# guitar_pedal.net
KiCad netlist of a schematic drawn in EAGLE
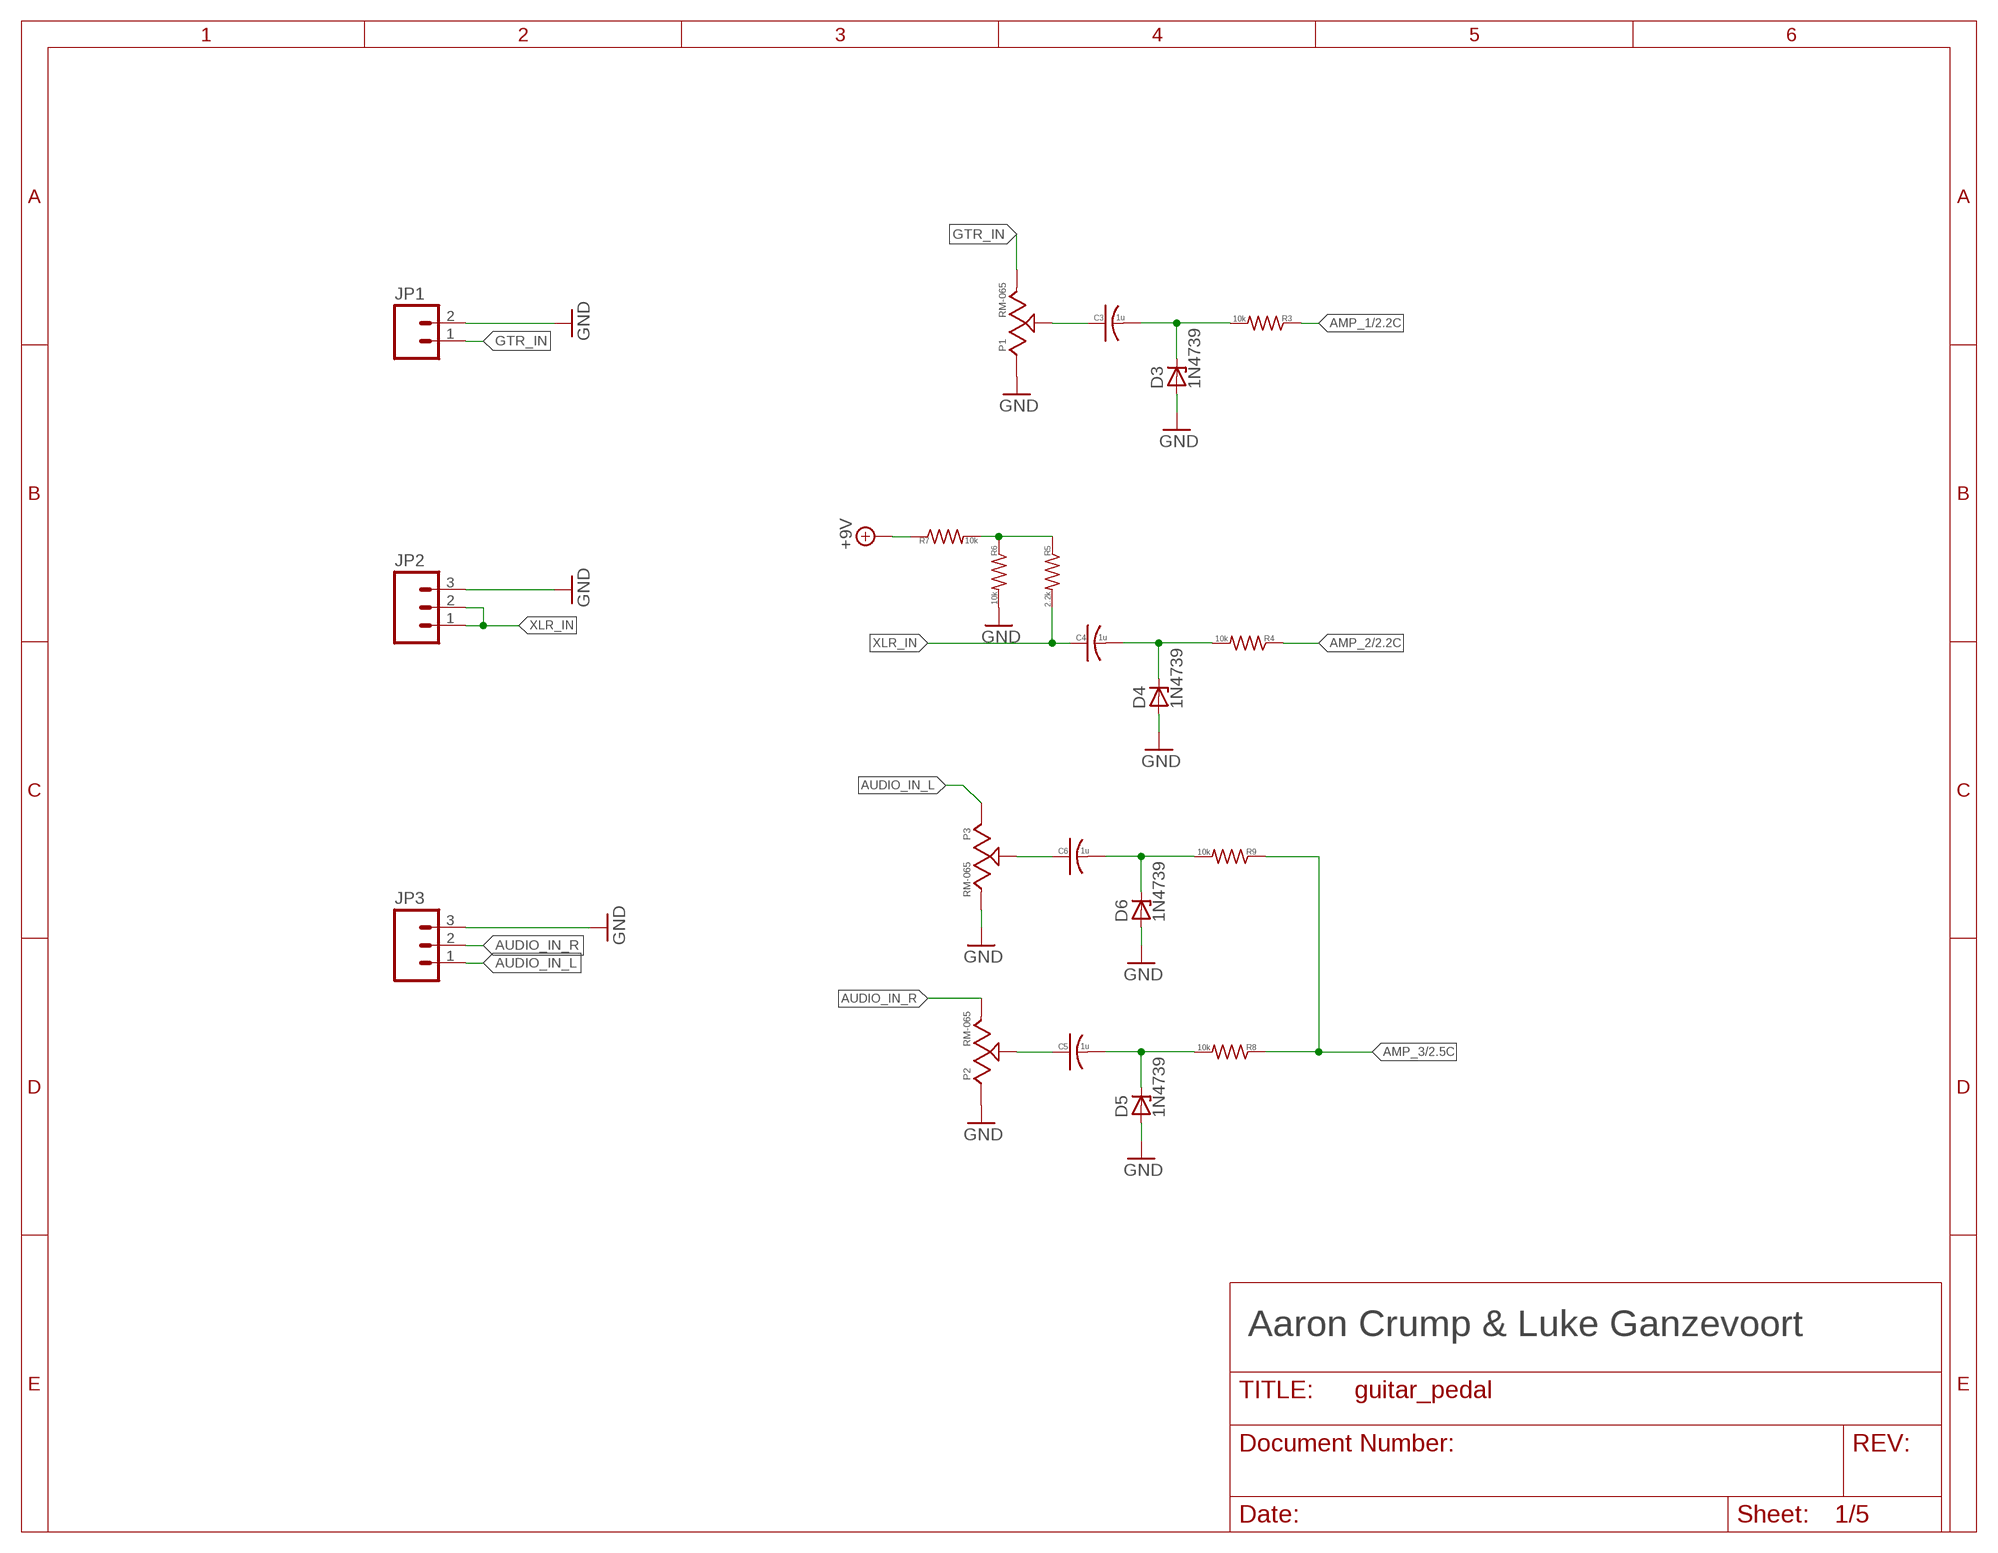
[diagram p0: schematic, sheet 1]
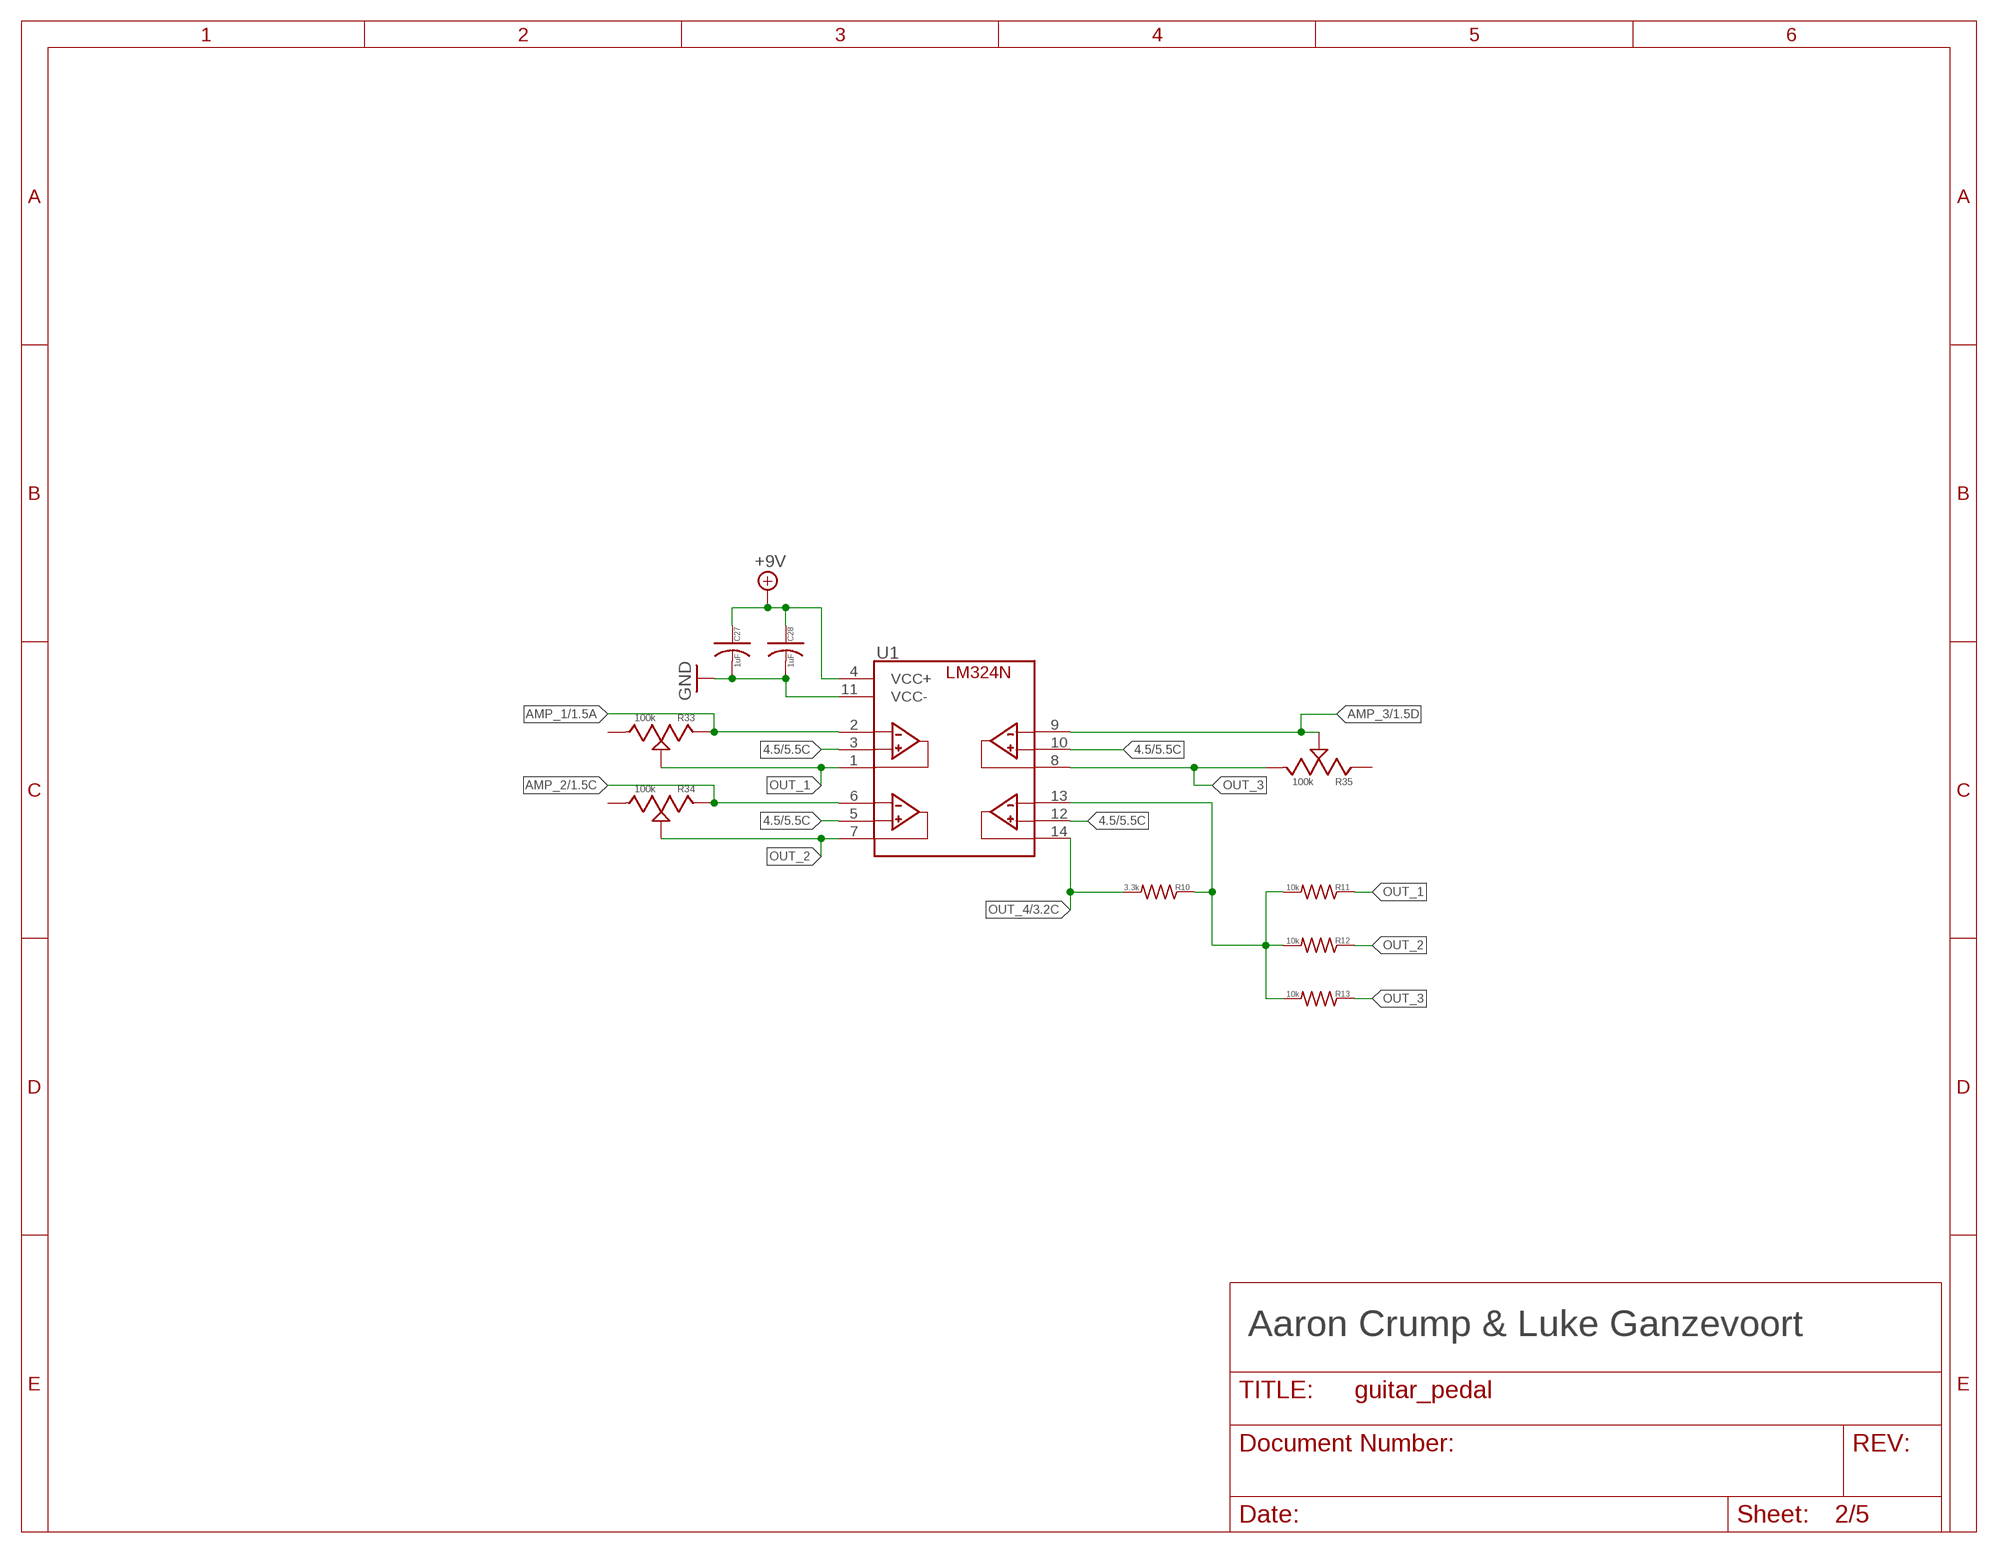
[diagram p1: schematic, sheet 2]
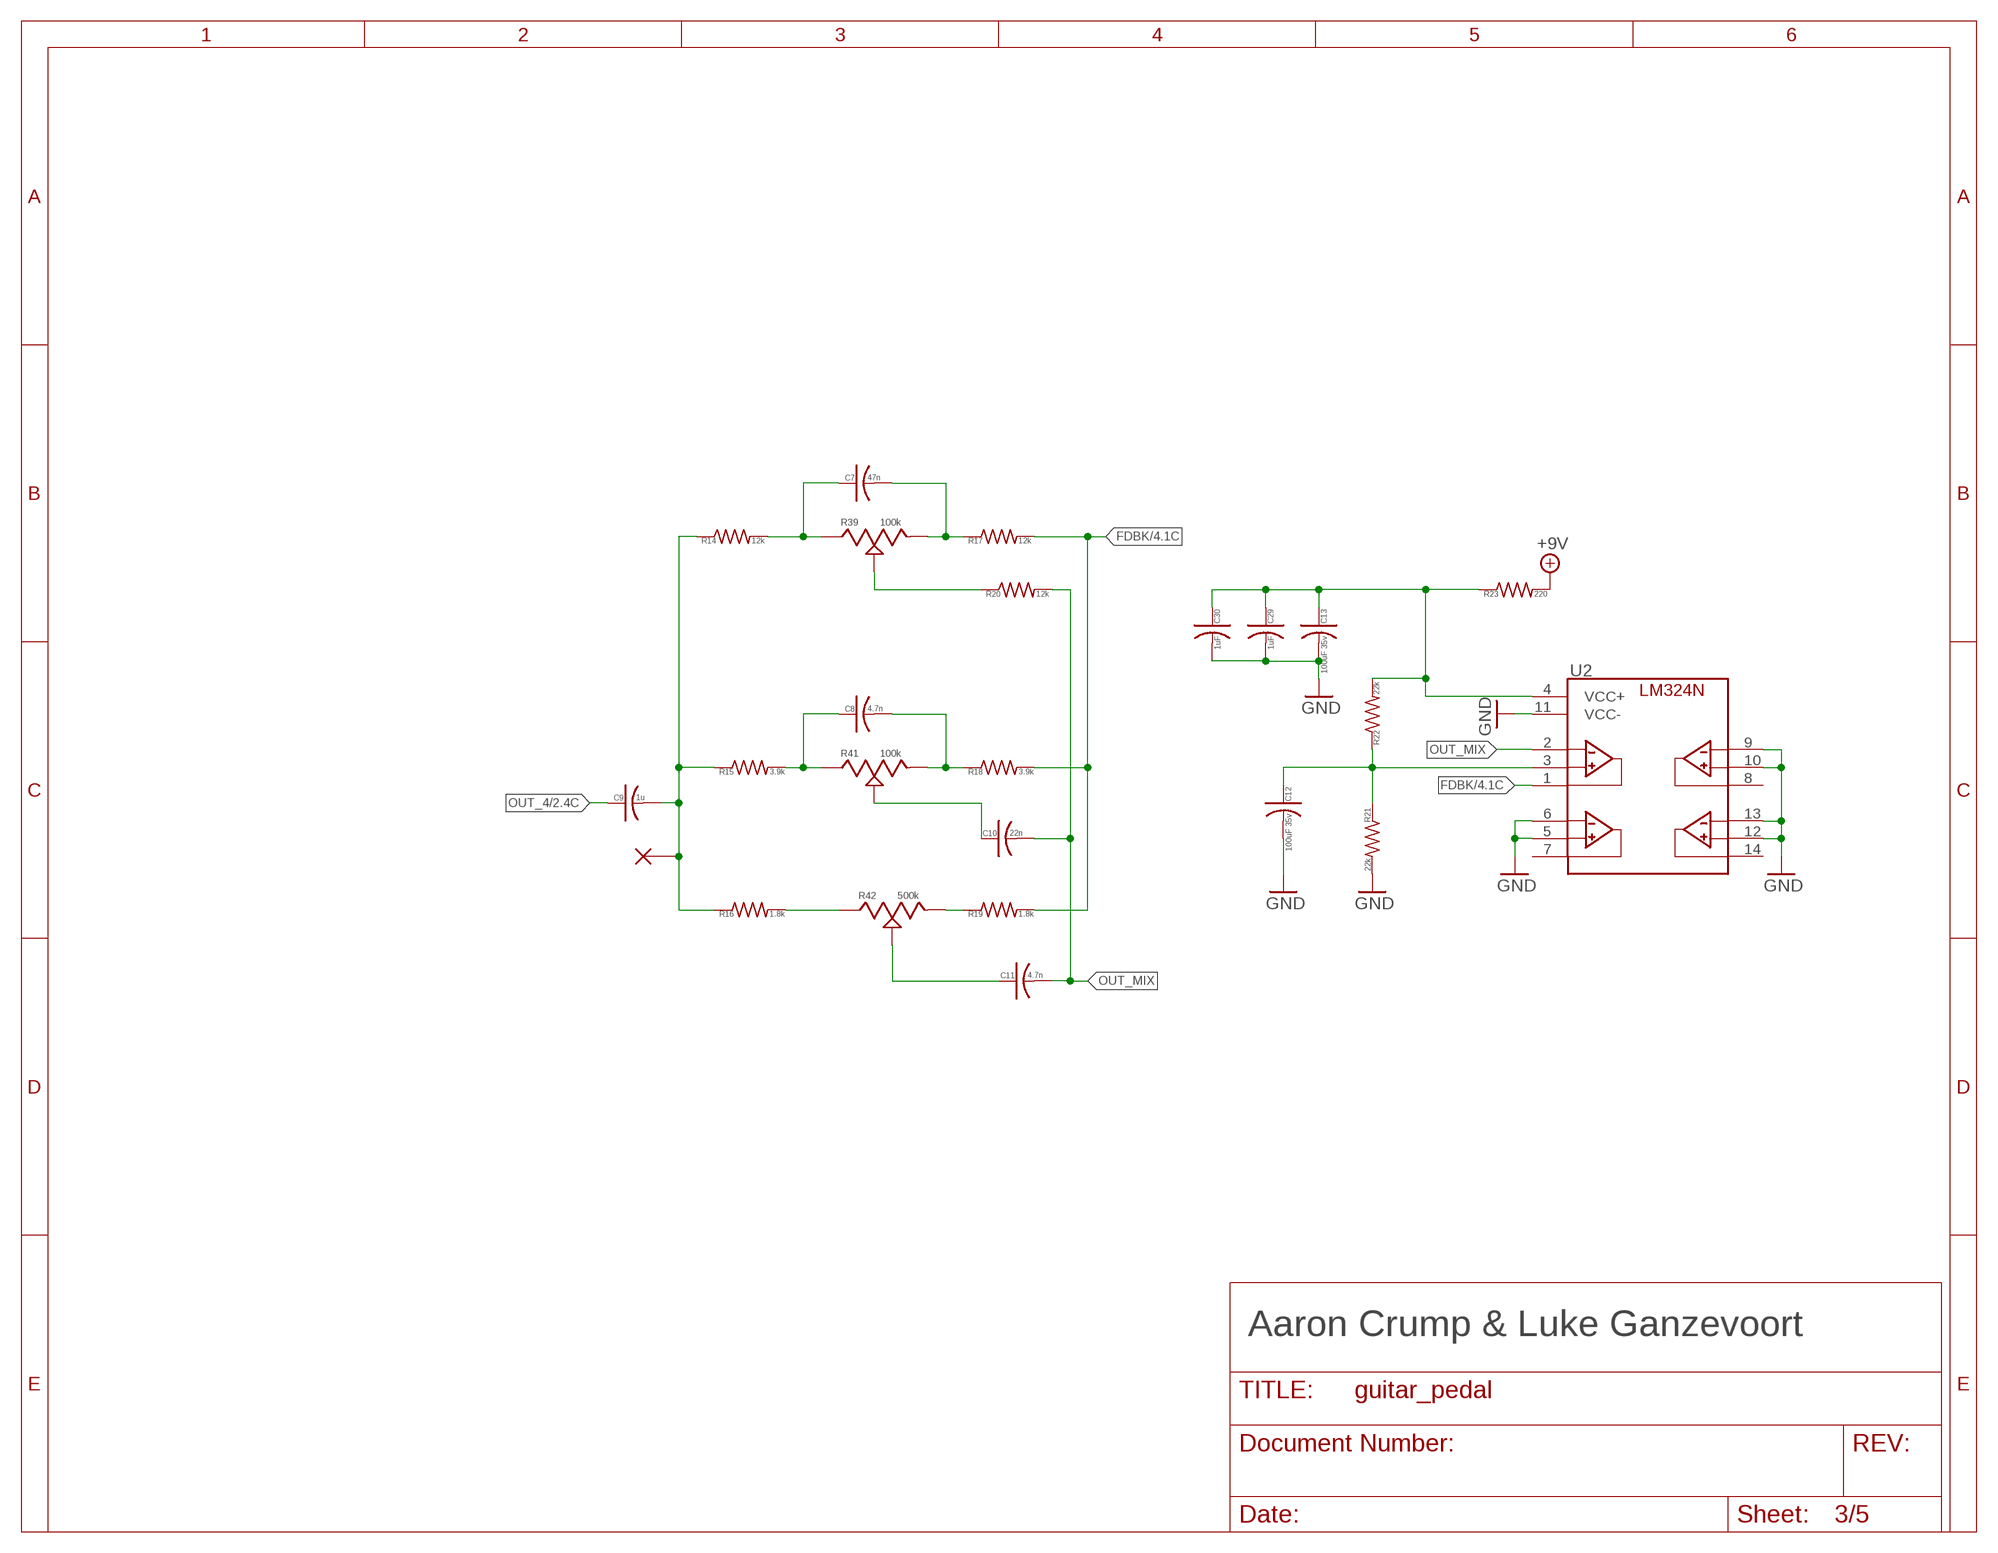
[diagram p2: schematic, sheet 3]
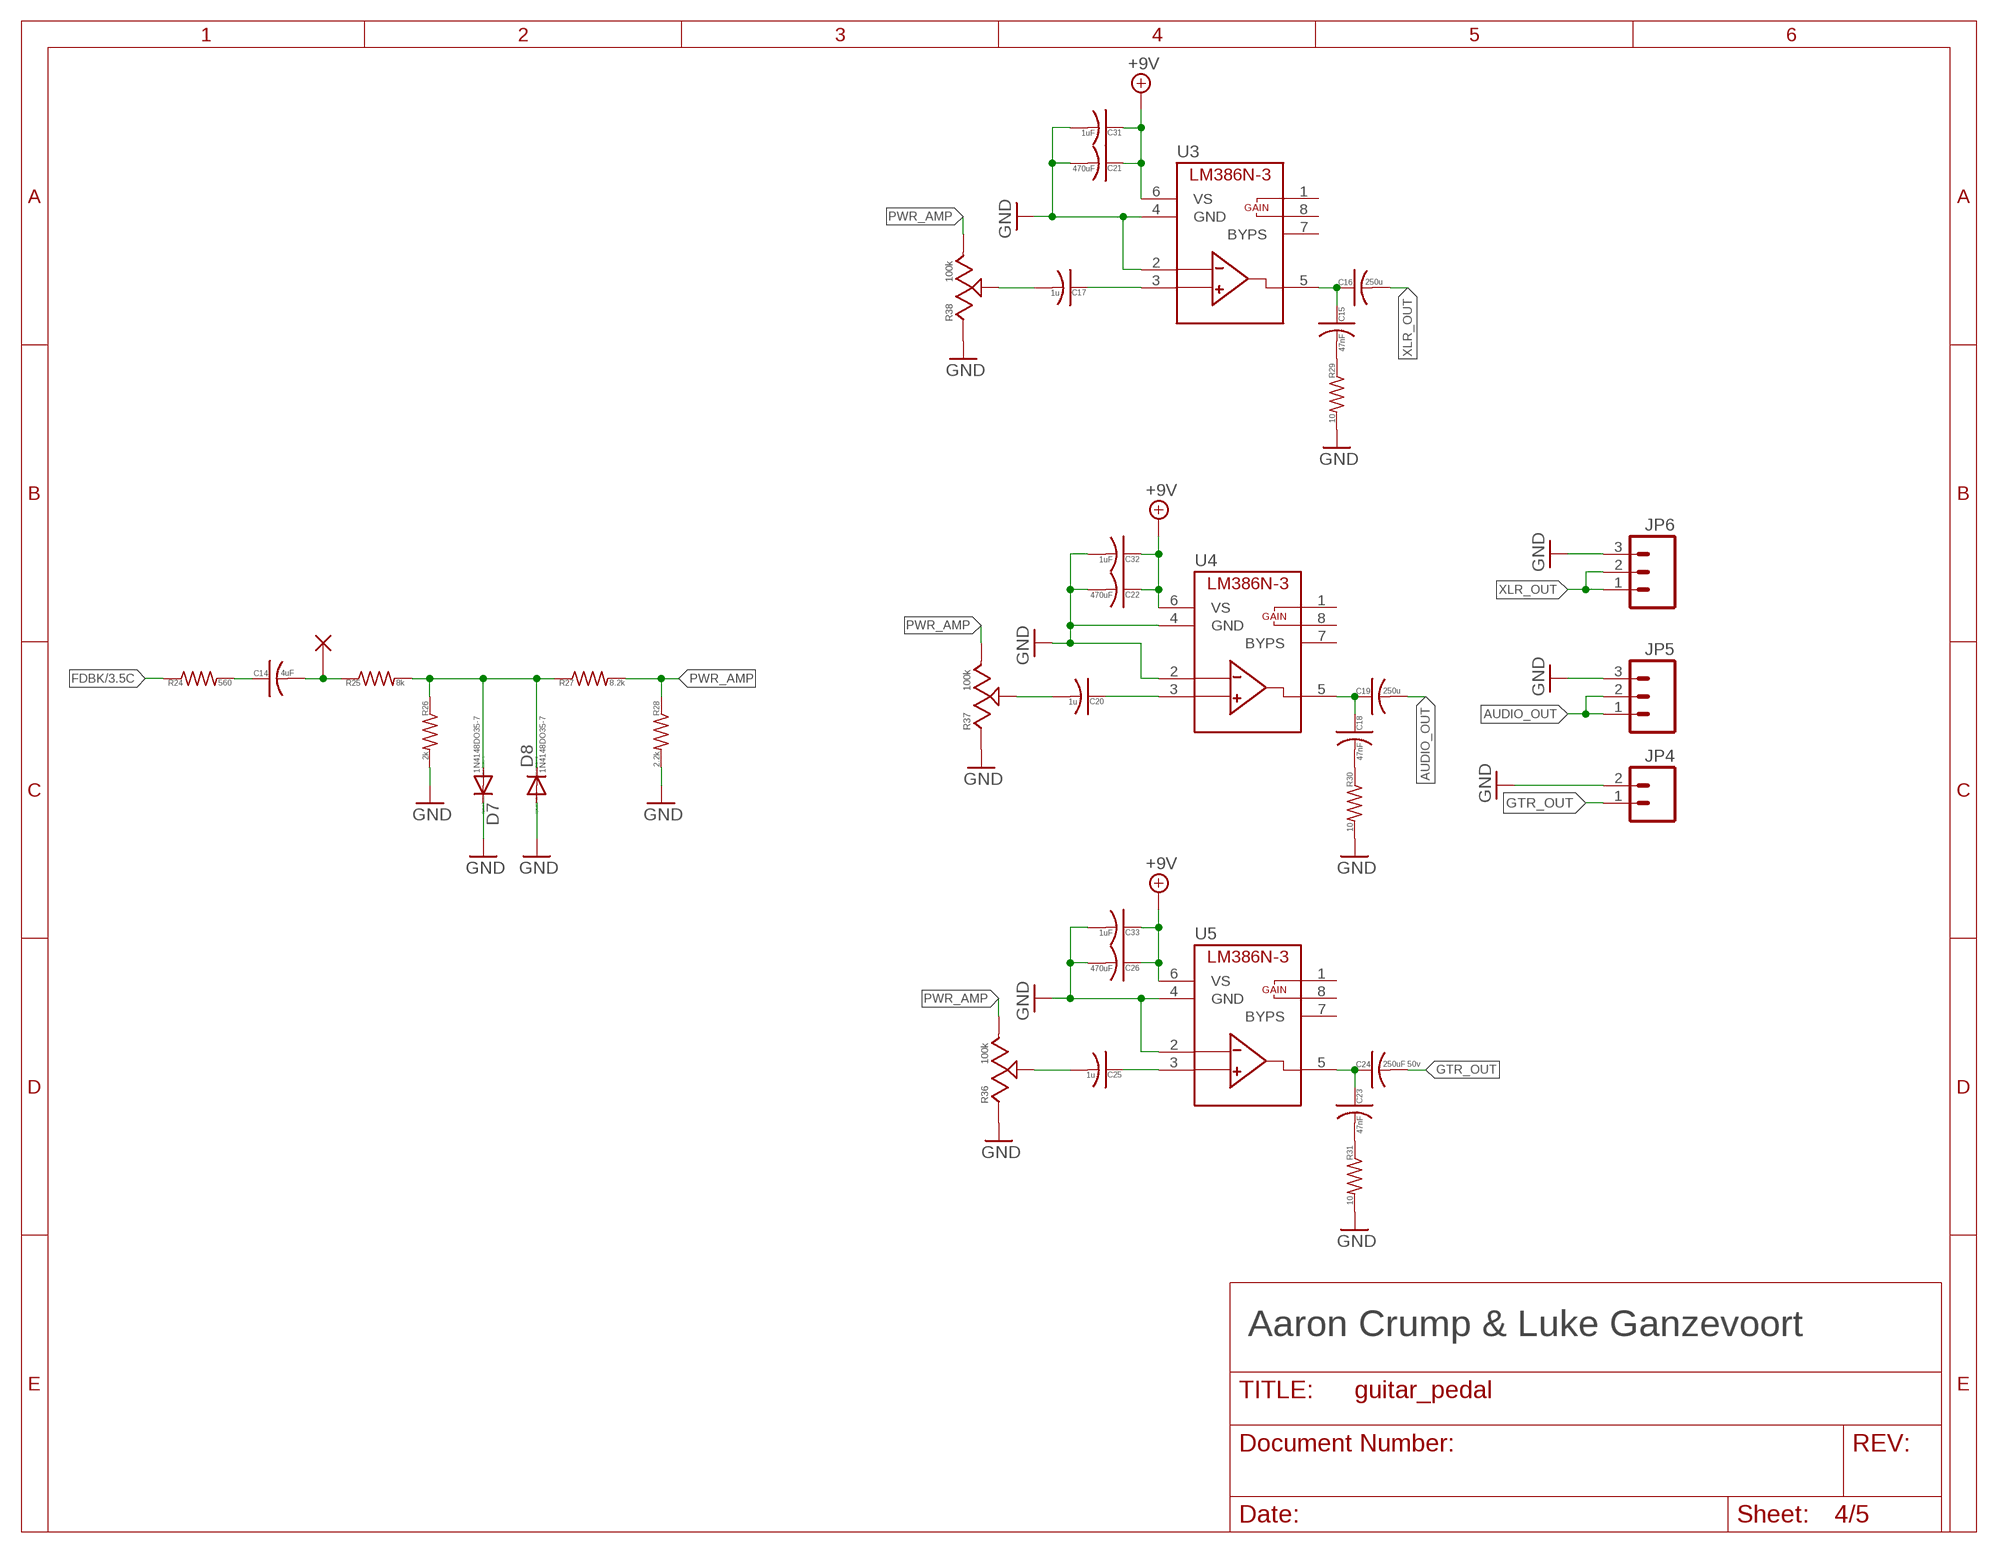
[diagram p3: schematic, sheet 4]
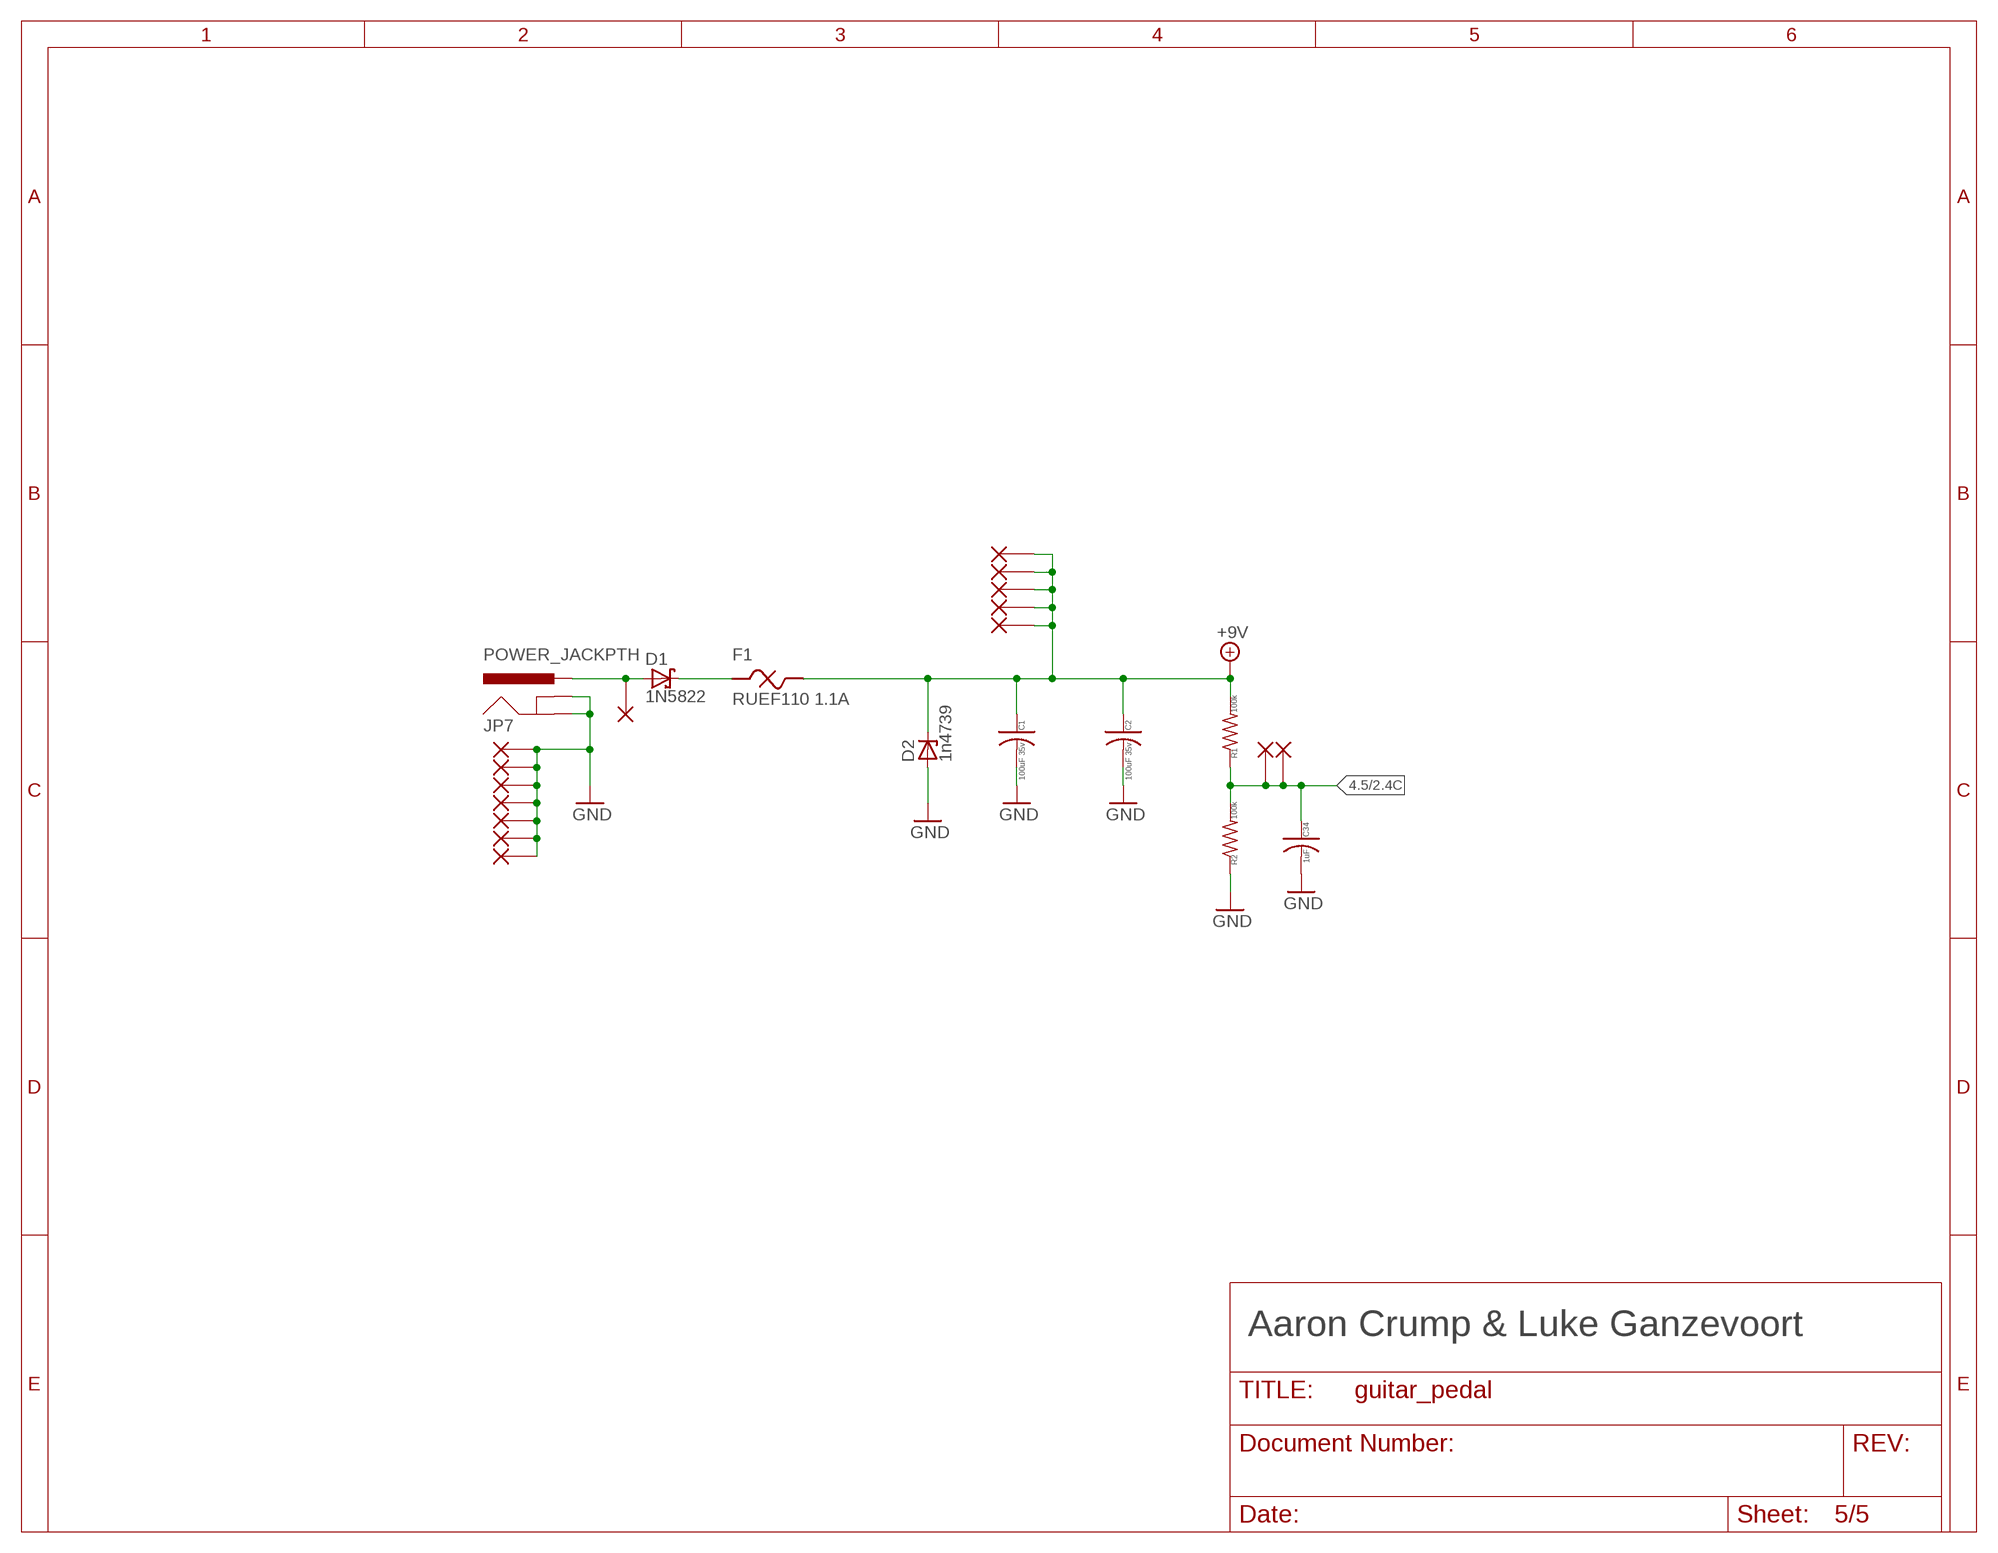
[diagram p4: schematic, sheet 5]

(export (version "E")
  (design (tool "Eeschema 10.0.6"))
  (components
    (comp (ref "C14")
      (value "4uF")
      (footprint "eagle-import:C0805")
      (libsource (lib "eagle-import") (part "CAPACITOR0805"))
    )
    (comp (ref "C15")
      (value "47nF")
      (footprint "eagle-import:C0805")
      (libsource (lib "eagle-import") (part "CAPACITOR0805"))
    )
    (comp (ref "C16")
      (value "250u")
      (footprint "eagle-import:CAN01")
      (libsource (lib "eagle-import") (part "CAP_CAN01"))
    )
    (comp (ref "C17")
      (value "1u")
      (footprint "eagle-import:C0805")
      (libsource (lib "eagle-import") (part "CAPACITOR0805"))
    )
    (comp (ref "C18")
      (value "47nF")
      (footprint "eagle-import:C0805")
      (libsource (lib "eagle-import") (part "CAPACITOR0805"))
    )
    (comp (ref "C19")
      (value "250u")
      (footprint "eagle-import:CAN01")
      (libsource (lib "eagle-import") (part "CAP_CAN01"))
    )
    (comp (ref "C20")
      (value "1u")
      (footprint "eagle-import:C0805")
      (libsource (lib "eagle-import") (part "CAPACITOR0805"))
    )
    (comp (ref "C21")
      (value "470uF")
      (footprint "eagle-import:CAN01")
      (libsource (lib "eagle-import") (part "CAP_CAN01"))
    )
    (comp (ref "C22")
      (value "470uF")
      (footprint "eagle-import:CAN01")
      (libsource (lib "eagle-import") (part "CAP_CAN01"))
    )
    (comp (ref "C23")
      (value "47nF")
      (footprint "eagle-import:C0805")
      (libsource (lib "eagle-import") (part "CAPACITOR0805"))
    )
    (comp (ref "C24")
      (value "250uF 50v")
      (footprint "eagle-import:CAN01")
      (libsource (lib "eagle-import") (part "CAP_CAN01"))
    )
    (comp (ref "C25")
      (value "1u")
      (footprint "eagle-import:C0805")
      (libsource (lib "eagle-import") (part "CAPACITOR0805"))
    )
    (comp (ref "C26")
      (value "470uF")
      (footprint "eagle-import:CAN01")
      (libsource (lib "eagle-import") (part "CAP_CAN01"))
    )
    (comp (ref "C31")
      (value "1uF")
      (footprint "eagle-import:C0805")
      (libsource (lib "eagle-import") (part "CAPACITOR0805"))
    )
    (comp (ref "C32")
      (value "1uF")
      (footprint "eagle-import:C0805")
      (libsource (lib "eagle-import") (part "CAPACITOR0805"))
    )
    (comp (ref "C33")
      (value "1uF")
      (footprint "eagle-import:C0805")
      (libsource (lib "eagle-import") (part "CAPACITOR0805"))
    )
    (comp (ref "D7")
      (value "1N4148DO35-7")
      (footprint "eagle-import:DO35-7")
      (libsource (lib "eagle-import") (part "1N4148DO35-7"))
    )
    (comp (ref "D8")
      (value "1N4148DO35-7")
      (footprint "eagle-import:DO35-7")
      (libsource (lib "eagle-import") (part "1N4148DO35-7"))
    )
    (comp (ref "JP4")
      (value "M02PTH")
      (footprint "eagle-import:1X02")
      (libsource (lib "eagle-import") (part "M02PTH"))
    )
    (comp (ref "JP5")
      (value "M03PTH")
      (footprint "eagle-import:1X03")
      (libsource (lib "eagle-import") (part "M03PTH"))
    )
    (comp (ref "JP6")
      (value "M03PTH")
      (footprint "eagle-import:1X03")
      (libsource (lib "eagle-import") (part "M03PTH"))
    )
    (comp (ref "R24")
      (value "560")
      (footprint "eagle-import:C0805")
      (libsource (lib "eagle-import") (part "RESISTOR0805"))
    )
    (comp (ref "R25")
      (value "8k")
      (footprint "eagle-import:C0805")
      (libsource (lib "eagle-import") (part "RESISTOR0805"))
    )
    (comp (ref "R26")
      (value "2k")
      (footprint "eagle-import:C0805")
      (libsource (lib "eagle-import") (part "RESISTOR0805"))
    )
    (comp (ref "R27")
      (value "8.2k")
      (footprint "eagle-import:C0805")
      (libsource (lib "eagle-import") (part "RESISTOR0805"))
    )
    (comp (ref "R28")
      (value "2.2k")
      (footprint "eagle-import:C0805")
      (libsource (lib "eagle-import") (part "RESISTOR0805"))
    )
    (comp (ref "R29")
      (value "10")
      (footprint "eagle-import:C0805")
      (libsource (lib "eagle-import") (part "RESISTOR0805"))
    )
    (comp (ref "R30")
      (value "10")
      (footprint "eagle-import:C0805")
      (libsource (lib "eagle-import") (part "RESISTOR0805"))
    )
    (comp (ref "R31")
      (value "10")
      (footprint "eagle-import:C0805")
      (libsource (lib "eagle-import") (part "RESISTOR0805"))
    )
    (comp (ref "R36")
      (value "100k")
      (footprint "eagle-import:1X03_LONGPADS")
      (libsource (lib "eagle-import") (part "POT"))
    )
    (comp (ref "R37")
      (value "100k")
      (footprint "eagle-import:1X03_LONGPADS")
      (libsource (lib "eagle-import") (part "POT"))
    )
    (comp (ref "R38")
      (value "100k")
      (footprint "eagle-import:1X03_LONGPADS")
      (libsource (lib "eagle-import") (part "POT"))
    )
    (comp (ref "U3")
      (value "LM386N-3")
      (footprint "eagle-import:DIL08")
      (libsource (lib "eagle-import") (part "LM386N-3"))
    )
    (comp (ref "U4")
      (value "LM386N-3")
      (footprint "eagle-import:DIL08")
      (libsource (lib "eagle-import") (part "LM386N-3"))
    )
    (comp (ref "U5")
      (value "LM386N-3")
      (footprint "eagle-import:DIL08")
      (libsource (lib "eagle-import") (part "LM386N-3"))
    )
    (comp (ref "V17")
      (value "EQout")
      (footprint "eagle-import:VIA1")
      (libsource (lib "eagle-import") (part "VIA1"))
    )
    (comp (ref "C1")
      (value "100uF 35v")
      (footprint "eagle-import:CAN_6MM")
      (libsource (lib "eagle-import") (part "CAPACITORCAN_6MM"))
    )
    (comp (ref "C2")
      (value "100uF 35v")
      (footprint "eagle-import:CAN_6MM")
      (libsource (lib "eagle-import") (part "CAPACITORCAN_6MM"))
    )
    (comp (ref "C34")
      (value "1uF")
      (footprint "eagle-import:C0805")
      (libsource (lib "eagle-import") (part "CAPACITOR0805"))
    )
    (comp (ref "D1")
      (value "1N5822")
      (footprint "eagle-import:DO201T15")
      (libsource (lib "eagle-import") (part "1N5822"))
    )
    (comp (ref "D2")
      (value "1n4739")
      (footprint "eagle-import:DO41-7")
      (libsource (lib "eagle-import") (part "1N4728"))
    )
    (comp (ref "F1")
      (value "RUEF110 1.1A")
      (footprint "eagle-import:RADIAL_PTC_RUEF110")
      (libsource (lib "eagle-import") (part "PTCRUEF110"))
    )
    (comp (ref "JP7")
      (value "POWER_JACKPTH")
      (footprint "eagle-import:POWER_JACK_PTH")
      (libsource (lib "eagle-import") (part "POWER_JACKPTH"))
    )
    (comp (ref "R1")
      (value "100k")
      (footprint "eagle-import:C0805")
      (libsource (lib "eagle-import") (part "RESISTOR0805"))
    )
    (comp (ref "R2")
      (value "100k")
      (footprint "eagle-import:C0805")
      (libsource (lib "eagle-import") (part "RESISTOR0805"))
    )
    (comp (ref "V1")
      (value "V+")
      (footprint "eagle-import:VIA1")
      (libsource (lib "eagle-import") (part "VIA1"))
    )
    (comp (ref "V3")
      (value "9v")
      (footprint "eagle-import:VIA1")
      (libsource (lib "eagle-import") (part "VIA1"))
    )
    (comp (ref "V4")
      (value "9v")
      (footprint "eagle-import:VIA1")
      (libsource (lib "eagle-import") (part "VIA1"))
    )
    (comp (ref "V5")
      (value "9v")
      (footprint "eagle-import:VIA1")
      (libsource (lib "eagle-import") (part "VIA1"))
    )
    (comp (ref "V6")
      (value "9v")
      (footprint "eagle-import:VIA1")
      (libsource (lib "eagle-import") (part "VIA1"))
    )
    (comp (ref "V7")
      (value "9v")
      (footprint "eagle-import:VIA1")
      (libsource (lib "eagle-import") (part "VIA1"))
    )
    (comp (ref "V8")
      (value "4v5")
      (footprint "eagle-import:VIA1")
      (libsource (lib "eagle-import") (part "VIA1"))
    )
    (comp (ref "V9")
      (value "4v5")
      (footprint "eagle-import:VIA1")
      (libsource (lib "eagle-import") (part "VIA1"))
    )
    (comp (ref "V10")
      (value "GND")
      (footprint "eagle-import:VIA1")
      (libsource (lib "eagle-import") (part "VIA1"))
    )
    (comp (ref "V11")
      (value "GND")
      (footprint "eagle-import:VIA1")
      (libsource (lib "eagle-import") (part "VIA1"))
    )
    (comp (ref "V12")
      (value "GND")
      (footprint "eagle-import:VIA1")
      (libsource (lib "eagle-import") (part "VIA1"))
    )
    (comp (ref "V13")
      (value "GND")
      (footprint "eagle-import:VIA1")
      (libsource (lib "eagle-import") (part "VIA1"))
    )
    (comp (ref "V14")
      (value "GND")
      (footprint "eagle-import:VIA1")
      (libsource (lib "eagle-import") (part "VIA1"))
    )
    (comp (ref "V15")
      (value "GND")
      (footprint "eagle-import:VIA1")
      (libsource (lib "eagle-import") (part "VIA1"))
    )
    (comp (ref "V16")
      (value "GND")
      (footprint "eagle-import:VIA1")
      (libsource (lib "eagle-import") (part "VIA1"))
    )
    (comp (ref "C7")
      (value "47n")
      (footprint "eagle-import:C0805")
      (libsource (lib "eagle-import") (part "CAPACITOR0805"))
    )
    (comp (ref "C8")
      (value "4.7n")
      (footprint "eagle-import:C0805")
      (libsource (lib "eagle-import") (part "CAPACITOR0805"))
    )
    (comp (ref "C9")
      (value "1u")
      (footprint "eagle-import:C0805")
      (libsource (lib "eagle-import") (part "CAPACITOR0805"))
    )
    (comp (ref "C10")
      (value "22n")
      (footprint "eagle-import:C0805")
      (libsource (lib "eagle-import") (part "CAPACITOR0805"))
    )
    (comp (ref "C11")
      (value "4.7n")
      (footprint "eagle-import:C0805")
      (libsource (lib "eagle-import") (part "CAPACITOR0805"))
    )
    (comp (ref "C12")
      (value "100uF 35v")
      (footprint "eagle-import:CAN_6MM")
      (libsource (lib "eagle-import") (part "CAPACITORCAN_6MM"))
    )
    (comp (ref "C13")
      (value "100uF 35v")
      (footprint "eagle-import:CAN_6MM")
      (libsource (lib "eagle-import") (part "CAPACITORCAN_6MM"))
    )
    (comp (ref "C29")
      (value "1uF")
      (footprint "eagle-import:C0805")
      (libsource (lib "eagle-import") (part "CAPACITOR0805"))
    )
    (comp (ref "C30")
      (value "1uF")
      (footprint "eagle-import:C0805")
      (libsource (lib "eagle-import") (part "CAPACITOR0805"))
    )
    (comp (ref "R14")
      (value "12k")
      (footprint "eagle-import:C0805")
      (libsource (lib "eagle-import") (part "RESISTOR0805"))
    )
    (comp (ref "R15")
      (value "3.9k")
      (footprint "eagle-import:C0805")
      (libsource (lib "eagle-import") (part "RESISTOR0805"))
    )
    (comp (ref "R16")
      (value "1.8k")
      (footprint "eagle-import:C0805")
      (libsource (lib "eagle-import") (part "RESISTOR0805"))
    )
    (comp (ref "R17")
      (value "12k")
      (footprint "eagle-import:C0805")
      (libsource (lib "eagle-import") (part "RESISTOR0805"))
    )
    (comp (ref "R18")
      (value "3.9k")
      (footprint "eagle-import:C0805")
      (libsource (lib "eagle-import") (part "RESISTOR0805"))
    )
    (comp (ref "R19")
      (value "1.8k")
      (footprint "eagle-import:C0805")
      (libsource (lib "eagle-import") (part "RESISTOR0805"))
    )
    (comp (ref "R20")
      (value "12k")
      (footprint "eagle-import:C0805")
      (libsource (lib "eagle-import") (part "RESISTOR0805"))
    )
    (comp (ref "R21")
      (value "22k")
      (footprint "eagle-import:C0805")
      (libsource (lib "eagle-import") (part "RESISTOR0805"))
    )
    (comp (ref "R22")
      (value "22k")
      (footprint "eagle-import:C0805")
      (libsource (lib "eagle-import") (part "RESISTOR0805"))
    )
    (comp (ref "R23")
      (value "220")
      (footprint "eagle-import:C0805")
      (libsource (lib "eagle-import") (part "RESISTOR0805"))
    )
    (comp (ref "R39")
      (value "100k")
      (footprint "eagle-import:1X03_LONGPADS")
      (libsource (lib "eagle-import") (part "POT"))
    )
    (comp (ref "R41")
      (value "100k")
      (footprint "eagle-import:1X03_LONGPADS")
      (libsource (lib "eagle-import") (part "POT"))
    )
    (comp (ref "R42")
      (value "500k")
      (footprint "eagle-import:1X03_LONGPADS")
      (libsource (lib "eagle-import") (part "POT"))
    )
    (comp (ref "U2")
      (value "LM324NSOIC-14")
      (footprint "eagle-import:SOIC-14")
      (libsource (lib "eagle-import") (part "LM324NSOIC-14"))
    )
    (comp (ref "V2")
      (value "EQin")
      (footprint "eagle-import:VIA1")
      (libsource (lib "eagle-import") (part "VIA1"))
    )
    (comp (ref "C27")
      (value "1uF")
      (footprint "eagle-import:C0805")
      (libsource (lib "eagle-import") (part "CAPACITOR0805"))
    )
    (comp (ref "C28")
      (value "1uF")
      (footprint "eagle-import:C0805")
      (libsource (lib "eagle-import") (part "CAPACITOR0805"))
    )
    (comp (ref "R10")
      (value "3.3k")
      (footprint "eagle-import:C0805")
      (libsource (lib "eagle-import") (part "RESISTOR0805"))
    )
    (comp (ref "R11")
      (value "10k")
      (footprint "eagle-import:C0805")
      (libsource (lib "eagle-import") (part "RESISTOR0805"))
    )
    (comp (ref "R12")
      (value "10k")
      (footprint "eagle-import:C0805")
      (libsource (lib "eagle-import") (part "RESISTOR0805"))
    )
    (comp (ref "R13")
      (value "10k")
      (footprint "eagle-import:C0805")
      (libsource (lib "eagle-import") (part "RESISTOR0805"))
    )
    (comp (ref "R33")
      (value "100k")
      (footprint "eagle-import:1X03_LONGPADS")
      (libsource (lib "eagle-import") (part "POT"))
    )
    (comp (ref "R34")
      (value "100k")
      (footprint "eagle-import:1X03_LONGPADS")
      (libsource (lib "eagle-import") (part "POT"))
    )
    (comp (ref "R35")
      (value "100k")
      (footprint "eagle-import:1X03_LONGPADS")
      (libsource (lib "eagle-import") (part "POT"))
    )
    (comp (ref "U1")
      (value "LM324NSOIC-14")
      (footprint "eagle-import:SOIC-14")
      (libsource (lib "eagle-import") (part "LM324NSOIC-14"))
    )
    (comp (ref "C3")
      (value "1u")
      (footprint "eagle-import:C0805")
      (libsource (lib "eagle-import") (part "CAPACITOR0805"))
    )
    (comp (ref "C4")
      (value "1u")
      (footprint "eagle-import:C0805")
      (libsource (lib "eagle-import") (part "CAPACITOR0805"))
    )
    (comp (ref "C5")
      (value "1u")
      (footprint "eagle-import:C0805")
      (libsource (lib "eagle-import") (part "CAPACITOR0805"))
    )
    (comp (ref "C6")
      (value "1u")
      (footprint "eagle-import:C0805")
      (libsource (lib "eagle-import") (part "CAPACITOR0805"))
    )
    (comp (ref "D3")
      (value "1N4739")
      (footprint "eagle-import:DO41-7")
      (libsource (lib "eagle-import") (part "1N4728"))
    )
    (comp (ref "D4")
      (value "1N4739")
      (footprint "eagle-import:DO41-7")
      (libsource (lib "eagle-import") (part "1N4728"))
    )
    (comp (ref "D5")
      (value "1N4739")
      (footprint "eagle-import:DO41-7")
      (libsource (lib "eagle-import") (part "1N4728"))
    )
    (comp (ref "D6")
      (value "1N4739")
      (footprint "eagle-import:DO41-7")
      (libsource (lib "eagle-import") (part "1N4728"))
    )
    (comp (ref "JP1")
      (value "M02PTH")
      (footprint "eagle-import:1X02")
      (libsource (lib "eagle-import") (part "M02PTH"))
    )
    (comp (ref "JP2")
      (value "M03PTH")
      (footprint "eagle-import:1X03")
      (libsource (lib "eagle-import") (part "M03PTH"))
    )
    (comp (ref "JP3")
      (value "M03PTH")
      (footprint "eagle-import:1X03")
      (libsource (lib "eagle-import") (part "M03PTH"))
    )
    (comp (ref "P1")
      (value "RM-065")
      (footprint "eagle-import:RM-065")
      (libsource (lib "eagle-import") (part "RM-065"))
    )
    (comp (ref "P2")
      (value "RM-065")
      (footprint "eagle-import:RM-065")
      (libsource (lib "eagle-import") (part "RM-065"))
    )
    (comp (ref "P3")
      (value "RM-065")
      (footprint "eagle-import:RM-065")
      (libsource (lib "eagle-import") (part "RM-065"))
    )
    (comp (ref "R3")
      (value "10k")
      (footprint "eagle-import:C0805")
      (libsource (lib "eagle-import") (part "RESISTOR0805"))
    )
    (comp (ref "R4")
      (value "10k")
      (footprint "eagle-import:C0805")
      (libsource (lib "eagle-import") (part "RESISTOR0805"))
    )
    (comp (ref "R5")
      (value "2.2k")
      (footprint "eagle-import:C0805")
      (libsource (lib "eagle-import") (part "RESISTOR0805"))
    )
    (comp (ref "R6")
      (value "10k")
      (footprint "eagle-import:C0805")
      (libsource (lib "eagle-import") (part "RESISTOR0805"))
    )
    (comp (ref "R7")
      (value "10k")
      (footprint "eagle-import:C0805")
      (libsource (lib "eagle-import") (part "RESISTOR0805"))
    )
    (comp (ref "R8")
      (value "10k")
      (footprint "eagle-import:C0805")
      (libsource (lib "eagle-import") (part "RESISTOR0805"))
    )
    (comp (ref "R9")
      (value "10k")
      (footprint "eagle-import:C0805")
      (libsource (lib "eagle-import") (part "RESISTOR0805"))
    )
  )
  (nets
    (net (code "1") (name "+9V") (class "Default")
      (node (ref "C1") (pin "P+") (pinfunction "POS_P+") (pintype "passive"))
      (node (ref "C2") (pin "P+") (pinfunction "POS_P+") (pintype "passive"))
      (node (ref "C21") (pin "+") (pinfunction "POS_+") (pintype "passive"))
      (node (ref "C22") (pin "+") (pinfunction "POS_+") (pintype "passive"))
      (node (ref "C26") (pin "+") (pinfunction "POS_+") (pintype "passive"))
      (node (ref "C27") (pin "1") (pinfunction "POS_1") (pintype "passive"))
      (node (ref "C28") (pin "1") (pinfunction "POS_1") (pintype "passive"))
      (node (ref "C31") (pin "1") (pinfunction "POS_1") (pintype "passive"))
      (node (ref "C32") (pin "1") (pinfunction "POS_1") (pintype "passive"))
      (node (ref "C33") (pin "1") (pinfunction "POS_1") (pintype "passive"))
      (node (ref "D2") (pin "C") (pinfunction "C_C") (pintype "passive"))
      (node (ref "F1") (pin "P$2") (pinfunction "2_P$2") (pintype "passive"))
      (node (ref "R1") (pin "2") (pinfunction "2_2") (pintype "passive"))
      (node (ref "R23") (pin "2") (pinfunction "2_2") (pintype "passive"))
      (node (ref "R7") (pin "1") (pinfunction "1_1") (pintype "passive"))
      (node (ref "U1") (pin "4") (pinfunction "VCC+_4") (pintype "bidirectional"))
      (node (ref "U3") (pin "6") (pinfunction "VS_6") (pintype "bidirectional"))
      (node (ref "U4") (pin "6") (pinfunction "VS_6") (pintype "bidirectional"))
      (node (ref "U5") (pin "6") (pinfunction "VS_6") (pintype "bidirectional"))
      (node (ref "V3") (pin "P$1") (pinfunction "P$1_P$1") (pintype "bidirectional"))
      (node (ref "V4") (pin "P$1") (pinfunction "P$1_P$1") (pintype "bidirectional"))
      (node (ref "V5") (pin "P$1") (pinfunction "P$1_P$1") (pintype "bidirectional"))
      (node (ref "V6") (pin "P$1") (pinfunction "P$1_P$1") (pintype "bidirectional"))
      (node (ref "V7") (pin "P$1") (pinfunction "P$1_P$1") (pintype "bidirectional"))
    )
    (net (code "2") (name "4.5") (class "Default")
      (node (ref "C34") (pin "1") (pinfunction "POS_1") (pintype "passive"))
      (node (ref "R1") (pin "1") (pinfunction "1_1") (pintype "passive"))
      (node (ref "R2") (pin "2") (pinfunction "2_2") (pintype "passive"))
      (node (ref "U1") (pin "10") (pinfunction "NINV_3_10") (pintype "bidirectional"))
      (node (ref "U1") (pin "12") (pinfunction "NINV_4_12") (pintype "bidirectional"))
      (node (ref "U1") (pin "3") (pinfunction "NINV_IN_1_3") (pintype "bidirectional"))
      (node (ref "U1") (pin "5") (pinfunction "NINV_IN_2_5") (pintype "bidirectional"))
      (node (ref "V8") (pin "P$1") (pinfunction "P$1_P$1") (pintype "bidirectional"))
      (node (ref "V9") (pin "P$1") (pinfunction "P$1_P$1") (pintype "bidirectional"))
    )
    (net (code "3") (name "AMP_1") (class "Default")
      (node (ref "R3") (pin "1") (pinfunction "1_1") (pintype "passive"))
      (node (ref "R33") (pin "1") (pinfunction "1_1") (pintype "passive"))
      (node (ref "U1") (pin "2") (pinfunction "INV_IN_1_2") (pintype "bidirectional"))
    )
    (net (code "4") (name "AMP_2") (class "Default")
      (node (ref "R34") (pin "1") (pinfunction "1_1") (pintype "passive"))
      (node (ref "R4") (pin "1") (pinfunction "1_1") (pintype "passive"))
      (node (ref "U1") (pin "6") (pinfunction "INV_IN_2_6") (pintype "bidirectional"))
    )
    (net (code "5") (name "AMP_3") (class "Default")
      (node (ref "R35") (pin "2") (pinfunction "W_2") (pintype "passive"))
      (node (ref "R8") (pin "1") (pinfunction "1_1") (pintype "passive"))
      (node (ref "R9") (pin "1") (pinfunction "1_1") (pintype "passive"))
      (node (ref "U1") (pin "9") (pinfunction "INV_3_9") (pintype "bidirectional"))
    )
    (net (code "6") (name "AUDIO_IN_L") (class "Default")
      (node (ref "JP3") (pin "1") (pinfunction "1_1") (pintype "passive"))
      (node (ref "P3") (pin "1") (pinfunction "1_1") (pintype "passive"))
    )
    (net (code "7") (name "AUDIO_IN_R") (class "Default")
      (node (ref "JP3") (pin "2") (pinfunction "2_2") (pintype "passive"))
      (node (ref "P2") (pin "3") (pinfunction "2_3") (pintype "passive"))
    )
    (net (code "8") (name "AUDIO_OUT") (class "Default")
      (node (ref "C19") (pin "-") (pinfunction "NEG_-") (pintype "passive"))
      (node (ref "JP5") (pin "1") (pinfunction "1_1") (pintype "passive"))
      (node (ref "JP5") (pin "2") (pinfunction "2_2") (pintype "passive"))
    )
    (net (code "9") (name "FDBK") (class "Default")
      (node (ref "R17") (pin "2") (pinfunction "2_2") (pintype "passive"))
      (node (ref "R18") (pin "2") (pinfunction "2_2") (pintype "passive"))
      (node (ref "R19") (pin "2") (pinfunction "2_2") (pintype "passive"))
      (node (ref "R24") (pin "1") (pinfunction "1_1") (pintype "passive"))
      (node (ref "U2") (pin "1") (pinfunction "OUT_1_1") (pintype "bidirectional"))
    )
    (net (code "10") (name "GND") (class "Default")
      (node (ref "C1") (pin "P-") (pinfunction "NEG_P-") (pintype "passive"))
      (node (ref "C12") (pin "P-") (pinfunction "NEG_P-") (pintype "passive"))
      (node (ref "C13") (pin "P-") (pinfunction "NEG_P-") (pintype "passive"))
      (node (ref "C2") (pin "P-") (pinfunction "NEG_P-") (pintype "passive"))
      (node (ref "C21") (pin "-") (pinfunction "NEG_-") (pintype "passive"))
      (node (ref "C22") (pin "-") (pinfunction "NEG_-") (pintype "passive"))
      (node (ref "C26") (pin "-") (pinfunction "NEG_-") (pintype "passive"))
      (node (ref "C27") (pin "2") (pinfunction "NEG_2") (pintype "passive"))
      (node (ref "C28") (pin "2") (pinfunction "NEG_2") (pintype "passive"))
      (node (ref "C29") (pin "2") (pinfunction "NEG_2") (pintype "passive"))
      (node (ref "C30") (pin "2") (pinfunction "NEG_2") (pintype "passive"))
      (node (ref "C31") (pin "2") (pinfunction "NEG_2") (pintype "passive"))
      (node (ref "C32") (pin "2") (pinfunction "NEG_2") (pintype "passive"))
      (node (ref "C33") (pin "2") (pinfunction "NEG_2") (pintype "passive"))
      (node (ref "C34") (pin "2") (pinfunction "NEG_2") (pintype "passive"))
      (node (ref "D2") (pin "A") (pinfunction "A_A") (pintype "passive"))
      (node (ref "D3") (pin "A") (pinfunction "A_A") (pintype "passive"))
      (node (ref "D4") (pin "A") (pinfunction "A_A") (pintype "passive"))
      (node (ref "D5") (pin "A") (pinfunction "A_A") (pintype "passive"))
      (node (ref "D6") (pin "A") (pinfunction "A_A") (pintype "passive"))
      (node (ref "D7") (pin "C") (pinfunction "C_C") (pintype "passive"))
      (node (ref "D8") (pin "A") (pinfunction "A_A") (pintype "passive"))
      (node (ref "JP1") (pin "2") (pinfunction "2_2") (pintype "passive"))
      (node (ref "JP2") (pin "3") (pinfunction "3_3") (pintype "passive"))
      (node (ref "JP3") (pin "3") (pinfunction "3_3") (pintype "passive"))
      (node (ref "JP4") (pin "2") (pinfunction "2_2") (pintype "passive"))
      (node (ref "JP5") (pin "3") (pinfunction "3_3") (pintype "passive"))
      (node (ref "JP6") (pin "3") (pinfunction "3_3") (pintype "passive"))
      (node (ref "JP7") (pin "GND") (pinfunction "GND_GND") (pintype "bidirectional"))
      (node (ref "JP7") (pin "GNDBREAK") (pinfunction "GNDBREAK_GNDBREAK") (pintype "bidirectional"))
      (node (ref "P1") (pin "1") (pinfunction "1_1") (pintype "passive"))
      (node (ref "P2") (pin "1") (pinfunction "1_1") (pintype "passive"))
      (node (ref "P3") (pin "3") (pinfunction "2_3") (pintype "passive"))
      (node (ref "R2") (pin "1") (pinfunction "1_1") (pintype "passive"))
      (node (ref "R21") (pin "2") (pinfunction "2_2") (pintype "passive"))
      (node (ref "R26") (pin "2") (pinfunction "2_2") (pintype "passive"))
      (node (ref "R28") (pin "2") (pinfunction "2_2") (pintype "passive"))
      (node (ref "R29") (pin "2") (pinfunction "2_2") (pintype "passive"))
      (node (ref "R30") (pin "2") (pinfunction "2_2") (pintype "passive"))
      (node (ref "R31") (pin "2") (pinfunction "2_2") (pintype "passive"))
      (node (ref "R36") (pin "1") (pinfunction "1_1") (pintype "passive"))
      (node (ref "R37") (pin "1") (pinfunction "1_1") (pintype "passive"))
      (node (ref "R38") (pin "1") (pinfunction "1_1") (pintype "passive"))
      (node (ref "R6") (pin "2") (pinfunction "2_2") (pintype "passive"))
      (node (ref "U1") (pin "11") (pinfunction "VCC-_11") (pintype "bidirectional"))
      (node (ref "U2") (pin "10") (pinfunction "NINV_3_10") (pintype "bidirectional"))
      (node (ref "U2") (pin "11") (pinfunction "VCC-_11") (pintype "bidirectional"))
      (node (ref "U2") (pin "12") (pinfunction "NINV_4_12") (pintype "bidirectional"))
      (node (ref "U2") (pin "13") (pinfunction "INV_4_13") (pintype "bidirectional"))
      (node (ref "U2") (pin "5") (pinfunction "NINV_IN_2_5") (pintype "bidirectional"))
      (node (ref "U2") (pin "6") (pinfunction "INV_IN_2_6") (pintype "bidirectional"))
      (node (ref "U2") (pin "9") (pinfunction "INV_3_9") (pintype "bidirectional"))
      (node (ref "U3") (pin "2") (pinfunction "-IN_2") (pintype "bidirectional"))
      (node (ref "U3") (pin "4") (pinfunction "GND_4") (pintype "bidirectional"))
      (node (ref "U4") (pin "2") (pinfunction "-IN_2") (pintype "bidirectional"))
      (node (ref "U4") (pin "4") (pinfunction "GND_4") (pintype "bidirectional"))
      (node (ref "U5") (pin "2") (pinfunction "-IN_2") (pintype "bidirectional"))
      (node (ref "U5") (pin "4") (pinfunction "GND_4") (pintype "bidirectional"))
      (node (ref "V10") (pin "P$1") (pinfunction "P$1_P$1") (pintype "bidirectional"))
      (node (ref "V11") (pin "P$1") (pinfunction "P$1_P$1") (pintype "bidirectional"))
      (node (ref "V12") (pin "P$1") (pinfunction "P$1_P$1") (pintype "bidirectional"))
      (node (ref "V13") (pin "P$1") (pinfunction "P$1_P$1") (pintype "bidirectional"))
      (node (ref "V14") (pin "P$1") (pinfunction "P$1_P$1") (pintype "bidirectional"))
      (node (ref "V15") (pin "P$1") (pinfunction "P$1_P$1") (pintype "bidirectional"))
      (node (ref "V16") (pin "P$1") (pinfunction "P$1_P$1") (pintype "bidirectional"))
    )
    (net (code "11") (name "GTR_IN") (class "Default")
      (node (ref "JP1") (pin "1") (pinfunction "1_1") (pintype "passive"))
      (node (ref "P1") (pin "3") (pinfunction "2_3") (pintype "passive"))
    )
    (net (code "12") (name "GTR_OUT") (class "Default")
      (node (ref "C24") (pin "-") (pinfunction "NEG_-") (pintype "passive"))
      (node (ref "JP4") (pin "1") (pinfunction "1_1") (pintype "passive"))
    )
    (net (code "13") (name "Net-(C3-NEG)") (class "Default")
      (node (ref "C3") (pin "2") (pinfunction "NEG_2") (pintype "passive"))
      (node (ref "D3") (pin "C") (pinfunction "C_C") (pintype "passive"))
      (node (ref "R3") (pin "2") (pinfunction "2_2") (pintype "passive"))
    )
    (net (code "14") (name "Net-(C3-POS)") (class "Default")
      (node (ref "C3") (pin "1") (pinfunction "POS_1") (pintype "passive"))
      (node (ref "P1") (pin "2") (pinfunction "W_2") (pintype "passive"))
    )
    (net (code "15") (name "Net-(C4-NEG)") (class "Default")
      (node (ref "C4") (pin "2") (pinfunction "NEG_2") (pintype "passive"))
      (node (ref "D4") (pin "C") (pinfunction "C_C") (pintype "passive"))
      (node (ref "R4") (pin "2") (pinfunction "2_2") (pintype "passive"))
    )
    (net (code "16") (name "Net-(C5-NEG)") (class "Default")
      (node (ref "C5") (pin "2") (pinfunction "NEG_2") (pintype "passive"))
      (node (ref "D5") (pin "C") (pinfunction "C_C") (pintype "passive"))
      (node (ref "R8") (pin "2") (pinfunction "2_2") (pintype "passive"))
    )
    (net (code "17") (name "Net-(C5-POS)") (class "Default")
      (node (ref "C5") (pin "1") (pinfunction "POS_1") (pintype "passive"))
      (node (ref "P2") (pin "2") (pinfunction "W_2") (pintype "passive"))
    )
    (net (code "18") (name "Net-(C6-NEG)") (class "Default")
      (node (ref "C6") (pin "2") (pinfunction "NEG_2") (pintype "passive"))
      (node (ref "D6") (pin "C") (pinfunction "C_C") (pintype "passive"))
      (node (ref "R9") (pin "2") (pinfunction "2_2") (pintype "passive"))
    )
    (net (code "19") (name "Net-(C6-POS)") (class "Default")
      (node (ref "C6") (pin "1") (pinfunction "POS_1") (pintype "passive"))
      (node (ref "P3") (pin "2") (pinfunction "W_2") (pintype "passive"))
    )
    (net (code "20") (name "Net-(C7-NEG)") (class "Default")
      (node (ref "C7") (pin "2") (pinfunction "NEG_2") (pintype "passive"))
      (node (ref "R17") (pin "1") (pinfunction "1_1") (pintype "passive"))
      (node (ref "R39") (pin "3") (pinfunction "2_3") (pintype "passive"))
    )
    (net (code "21") (name "Net-(C7-POS)") (class "Default")
      (node (ref "C7") (pin "1") (pinfunction "POS_1") (pintype "passive"))
      (node (ref "R14") (pin "2") (pinfunction "2_2") (pintype "passive"))
      (node (ref "R39") (pin "1") (pinfunction "1_1") (pintype "passive"))
    )
    (net (code "22") (name "Net-(C8-NEG)") (class "Default")
      (node (ref "C8") (pin "2") (pinfunction "NEG_2") (pintype "passive"))
      (node (ref "R18") (pin "1") (pinfunction "1_1") (pintype "passive"))
      (node (ref "R41") (pin "3") (pinfunction "2_3") (pintype "passive"))
    )
    (net (code "23") (name "Net-(C8-POS)") (class "Default")
      (node (ref "C8") (pin "1") (pinfunction "POS_1") (pintype "passive"))
      (node (ref "R15") (pin "2") (pinfunction "2_2") (pintype "passive"))
      (node (ref "R41") (pin "1") (pinfunction "1_1") (pintype "passive"))
    )
    (net (code "24") (name "Net-(C9-NEG)") (class "Default")
      (node (ref "C9") (pin "2") (pinfunction "NEG_2") (pintype "passive"))
      (node (ref "R14") (pin "1") (pinfunction "1_1") (pintype "passive"))
      (node (ref "R15") (pin "1") (pinfunction "1_1") (pintype "passive"))
      (node (ref "R16") (pin "1") (pinfunction "1_1") (pintype "passive"))
      (node (ref "V2") (pin "P$1") (pinfunction "P$1_P$1") (pintype "bidirectional"))
    )
    (net (code "25") (name "Net-(C10-POS)") (class "Default")
      (node (ref "C10") (pin "1") (pinfunction "POS_1") (pintype "passive"))
      (node (ref "R41") (pin "2") (pinfunction "W_2") (pintype "passive"))
    )
    (net (code "26") (name "Net-(C11-POS)") (class "Default")
      (node (ref "C11") (pin "1") (pinfunction "POS_1") (pintype "passive"))
      (node (ref "R42") (pin "2") (pinfunction "W_2") (pintype "passive"))
    )
    (net (code "27") (name "Net-(C12-POS)") (class "Default")
      (node (ref "C12") (pin "P+") (pinfunction "POS_P+") (pintype "passive"))
      (node (ref "R21") (pin "1") (pinfunction "1_1") (pintype "passive"))
      (node (ref "R22") (pin "1") (pinfunction "1_1") (pintype "passive"))
      (node (ref "U2") (pin "3") (pinfunction "NINV_IN_1_3") (pintype "bidirectional"))
    )
    (net (code "28") (name "Net-(C13-POS)") (class "Default")
      (node (ref "C13") (pin "P+") (pinfunction "POS_P+") (pintype "passive"))
      (node (ref "C29") (pin "1") (pinfunction "POS_1") (pintype "passive"))
      (node (ref "C30") (pin "1") (pinfunction "POS_1") (pintype "passive"))
      (node (ref "R22") (pin "2") (pinfunction "2_2") (pintype "passive"))
      (node (ref "R23") (pin "1") (pinfunction "1_1") (pintype "passive"))
      (node (ref "U2") (pin "4") (pinfunction "VCC+_4") (pintype "bidirectional"))
    )
    (net (code "29") (name "Net-(C14-NEG)") (class "Default")
      (node (ref "C14") (pin "2") (pinfunction "NEG_2") (pintype "passive"))
      (node (ref "R25") (pin "1") (pinfunction "1_1") (pintype "passive"))
      (node (ref "V17") (pin "P$1") (pinfunction "P$1_P$1") (pintype "bidirectional"))
    )
    (net (code "30") (name "Net-(C14-POS)") (class "Default")
      (node (ref "C14") (pin "1") (pinfunction "POS_1") (pintype "passive"))
      (node (ref "R24") (pin "2") (pinfunction "2_2") (pintype "passive"))
    )
    (net (code "31") (name "Net-(C15-NEG)") (class "Default")
      (node (ref "C15") (pin "2") (pinfunction "NEG_2") (pintype "passive"))
      (node (ref "R29") (pin "1") (pinfunction "1_1") (pintype "passive"))
    )
    (net (code "32") (name "Net-(C15-POS)") (class "Default")
      (node (ref "C15") (pin "1") (pinfunction "POS_1") (pintype "passive"))
      (node (ref "C16") (pin "+") (pinfunction "POS_+") (pintype "passive"))
      (node (ref "U3") (pin "5") (pinfunction "VOUT_5") (pintype "bidirectional"))
    )
    (net (code "33") (name "Net-(C17-NEG)") (class "Default")
      (node (ref "C17") (pin "2") (pinfunction "NEG_2") (pintype "passive"))
      (node (ref "R38") (pin "2") (pinfunction "W_2") (pintype "passive"))
    )
    (net (code "34") (name "Net-(C17-POS)") (class "Default")
      (node (ref "C17") (pin "1") (pinfunction "POS_1") (pintype "passive"))
      (node (ref "U3") (pin "3") (pinfunction "+IN_3") (pintype "bidirectional"))
    )
    (net (code "35") (name "Net-(C18-NEG)") (class "Default")
      (node (ref "C18") (pin "2") (pinfunction "NEG_2") (pintype "passive"))
      (node (ref "R30") (pin "1") (pinfunction "1_1") (pintype "passive"))
    )
    (net (code "36") (name "Net-(C18-POS)") (class "Default")
      (node (ref "C18") (pin "1") (pinfunction "POS_1") (pintype "passive"))
      (node (ref "C19") (pin "+") (pinfunction "POS_+") (pintype "passive"))
      (node (ref "U4") (pin "5") (pinfunction "VOUT_5") (pintype "bidirectional"))
    )
    (net (code "37") (name "Net-(C20-NEG)") (class "Default")
      (node (ref "C20") (pin "2") (pinfunction "NEG_2") (pintype "passive"))
      (node (ref "R37") (pin "2") (pinfunction "W_2") (pintype "passive"))
    )
    (net (code "38") (name "Net-(C20-POS)") (class "Default")
      (node (ref "C20") (pin "1") (pinfunction "POS_1") (pintype "passive"))
      (node (ref "U4") (pin "3") (pinfunction "+IN_3") (pintype "bidirectional"))
    )
    (net (code "39") (name "Net-(C23-NEG)") (class "Default")
      (node (ref "C23") (pin "2") (pinfunction "NEG_2") (pintype "passive"))
      (node (ref "R31") (pin "1") (pinfunction "1_1") (pintype "passive"))
    )
    (net (code "40") (name "Net-(C23-POS)") (class "Default")
      (node (ref "C23") (pin "1") (pinfunction "POS_1") (pintype "passive"))
      (node (ref "C24") (pin "+") (pinfunction "POS_+") (pintype "passive"))
      (node (ref "U5") (pin "5") (pinfunction "VOUT_5") (pintype "bidirectional"))
    )
    (net (code "41") (name "Net-(C25-NEG)") (class "Default")
      (node (ref "C25") (pin "2") (pinfunction "NEG_2") (pintype "passive"))
      (node (ref "R36") (pin "2") (pinfunction "W_2") (pintype "passive"))
    )
    (net (code "42") (name "Net-(C25-POS)") (class "Default")
      (node (ref "C25") (pin "1") (pinfunction "POS_1") (pintype "passive"))
      (node (ref "U5") (pin "3") (pinfunction "+IN_3") (pintype "bidirectional"))
    )
    (net (code "43") (name "Net-(D1-PadA)") (class "Default")
      (node (ref "D1") (pin "A") (pinfunction "A_A") (pintype "passive"))
      (node (ref "JP7") (pin "PWR") (pinfunction "PWR_PWR") (pintype "bidirectional"))
      (node (ref "V1") (pin "P$1") (pinfunction "P$1_P$1") (pintype "bidirectional"))
    )
    (net (code "44") (name "Net-(D7-PadA)") (class "Default")
      (node (ref "D7") (pin "A") (pinfunction "A_A") (pintype "passive"))
      (node (ref "D8") (pin "C") (pinfunction "C_C") (pintype "passive"))
      (node (ref "R25") (pin "2") (pinfunction "2_2") (pintype "passive"))
      (node (ref "R26") (pin "1") (pinfunction "1_1") (pintype "passive"))
      (node (ref "R27") (pin "1") (pinfunction "1_1") (pintype "passive"))
    )
    (net (code "45") (name "Net-(F1-1)") (class "Default")
      (node (ref "D1") (pin "C") (pinfunction "C_C") (pintype "passive"))
      (node (ref "F1") (pin "P$1") (pinfunction "1_P$1") (pintype "passive"))
    )
    (net (code "46") (name "Net-(R5-Pad1)") (class "Default")
      (node (ref "R5") (pin "1") (pinfunction "1_1") (pintype "passive"))
      (node (ref "R6") (pin "1") (pinfunction "1_1") (pintype "passive"))
      (node (ref "R7") (pin "2") (pinfunction "2_2") (pintype "passive"))
    )
    (net (code "47") (name "Net-(R16-Pad2)") (class "Default")
      (node (ref "R16") (pin "2") (pinfunction "2_2") (pintype "passive"))
      (node (ref "R42") (pin "1") (pinfunction "1_1") (pintype "passive"))
    )
    (net (code "48") (name "Net-(R39-W)") (class "Default")
      (node (ref "R20") (pin "1") (pinfunction "1_1") (pintype "passive"))
      (node (ref "R39") (pin "2") (pinfunction "W_2") (pintype "passive"))
    )
    (net (code "49") (name "Net-(R42-2)") (class "Default")
      (node (ref "R19") (pin "1") (pinfunction "1_1") (pintype "passive"))
      (node (ref "R42") (pin "3") (pinfunction "2_3") (pintype "passive"))
    )
    (net (code "50") (name "Net-(U1-INV_4)") (class "Default")
      (node (ref "R10") (pin "1") (pinfunction "1_1") (pintype "passive"))
      (node (ref "R11") (pin "2") (pinfunction "2_2") (pintype "passive"))
      (node (ref "R12") (pin "2") (pinfunction "2_2") (pintype "passive"))
      (node (ref "R13") (pin "2") (pinfunction "2_2") (pintype "passive"))
      (node (ref "U1") (pin "13") (pinfunction "INV_4_13") (pintype "bidirectional"))
    )
    (net (code "51") (name "OUT_1") (class "Default")
      (node (ref "R11") (pin "1") (pinfunction "1_1") (pintype "passive"))
      (node (ref "R33") (pin "2") (pinfunction "W_2") (pintype "passive"))
      (node (ref "U1") (pin "1") (pinfunction "OUT_1_1") (pintype "bidirectional"))
    )
    (net (code "52") (name "OUT_2") (class "Default")
      (node (ref "R12") (pin "1") (pinfunction "1_1") (pintype "passive"))
      (node (ref "R34") (pin "2") (pinfunction "W_2") (pintype "passive"))
      (node (ref "U1") (pin "7") (pinfunction "OUT_2_7") (pintype "bidirectional"))
    )
    (net (code "53") (name "OUT_3") (class "Default")
      (node (ref "R13") (pin "1") (pinfunction "1_1") (pintype "passive"))
      (node (ref "R35") (pin "3") (pinfunction "2_3") (pintype "passive"))
      (node (ref "U1") (pin "8") (pinfunction "OUT_3_8") (pintype "bidirectional"))
    )
    (net (code "54") (name "OUT_4") (class "Default")
      (node (ref "C9") (pin "1") (pinfunction "POS_1") (pintype "passive"))
      (node (ref "R10") (pin "2") (pinfunction "2_2") (pintype "passive"))
      (node (ref "U1") (pin "14") (pinfunction "OUT_4_14") (pintype "bidirectional"))
    )
    (net (code "55") (name "OUT_MIX") (class "Default")
      (node (ref "C10") (pin "2") (pinfunction "NEG_2") (pintype "passive"))
      (node (ref "C11") (pin "2") (pinfunction "NEG_2") (pintype "passive"))
      (node (ref "R20") (pin "2") (pinfunction "2_2") (pintype "passive"))
      (node (ref "U2") (pin "2") (pinfunction "INV_IN_1_2") (pintype "bidirectional"))
    )
    (net (code "56") (name "PWR_AMP") (class "Default")
      (node (ref "R27") (pin "2") (pinfunction "2_2") (pintype "passive"))
      (node (ref "R28") (pin "1") (pinfunction "1_1") (pintype "passive"))
      (node (ref "R36") (pin "3") (pinfunction "2_3") (pintype "passive"))
      (node (ref "R37") (pin "3") (pinfunction "2_3") (pintype "passive"))
      (node (ref "R38") (pin "3") (pinfunction "2_3") (pintype "passive"))
    )
    (net (code "57") (name "XLR_IN") (class "Default")
      (node (ref "C4") (pin "1") (pinfunction "POS_1") (pintype "passive"))
      (node (ref "JP2") (pin "1") (pinfunction "1_1") (pintype "passive"))
      (node (ref "JP2") (pin "2") (pinfunction "2_2") (pintype "passive"))
      (node (ref "R5") (pin "2") (pinfunction "2_2") (pintype "passive"))
    )
    (net (code "58") (name "XLR_OUT") (class "Default")
      (node (ref "C16") (pin "-") (pinfunction "NEG_-") (pintype "passive"))
      (node (ref "JP6") (pin "1") (pinfunction "1_1") (pintype "passive"))
      (node (ref "JP6") (pin "2") (pinfunction "2_2") (pintype "passive"))
    )
    (net (code "59") (name "unconnected-(R33-2-Pad3)") (class "Default")
      (node (ref "R33") (pin "3") (pinfunction "2_3") (pintype "passive"))
    )
    (net (code "60") (name "unconnected-(R34-2-Pad3)") (class "Default")
      (node (ref "R34") (pin "3") (pinfunction "2_3") (pintype "passive"))
    )
    (net (code "61") (name "unconnected-(R35-Pad1)") (class "Default")
      (node (ref "R35") (pin "1") (pinfunction "1_1") (pintype "passive"))
    )
    (net (code "62") (name "unconnected-(U2-OUT_2-Pad7)") (class "Default")
      (node (ref "U2") (pin "7") (pinfunction "OUT_2_7") (pintype "bidirectional"))
    )
    (net (code "63") (name "unconnected-(U2-OUT_3-Pad8)") (class "Default")
      (node (ref "U2") (pin "8") (pinfunction "OUT_3_8") (pintype "bidirectional"))
    )
    (net (code "64") (name "unconnected-(U2-OUT_4-Pad14)") (class "Default")
      (node (ref "U2") (pin "14") (pinfunction "OUT_4_14") (pintype "bidirectional"))
    )
    (net (code "65") (name "unconnected-(U3-BYPS-Pad7)") (class "Default")
      (node (ref "U3") (pin "7") (pinfunction "BYPS_7") (pintype "bidirectional"))
    )
    (net (code "66") (name "unconnected-(U3-GN-Pad1)") (class "Default")
      (node (ref "U3") (pin "1") (pinfunction "GN_1") (pintype "bidirectional"))
    )
    (net (code "67") (name "unconnected-(U3-GN2-Pad8)") (class "Default")
      (node (ref "U3") (pin "8") (pinfunction "GN2_8") (pintype "bidirectional"))
    )
    (net (code "68") (name "unconnected-(U4-BYPS-Pad7)") (class "Default")
      (node (ref "U4") (pin "7") (pinfunction "BYPS_7") (pintype "bidirectional"))
    )
    (net (code "69") (name "unconnected-(U4-GN-Pad1)") (class "Default")
      (node (ref "U4") (pin "1") (pinfunction "GN_1") (pintype "bidirectional"))
    )
    (net (code "70") (name "unconnected-(U4-GN2-Pad8)") (class "Default")
      (node (ref "U4") (pin "8") (pinfunction "GN2_8") (pintype "bidirectional"))
    )
    (net (code "71") (name "unconnected-(U5-BYPS-Pad7)") (class "Default")
      (node (ref "U5") (pin "7") (pinfunction "BYPS_7") (pintype "bidirectional"))
    )
    (net (code "72") (name "unconnected-(U5-GN-Pad1)") (class "Default")
      (node (ref "U5") (pin "1") (pinfunction "GN_1") (pintype "bidirectional"))
    )
    (net (code "73") (name "unconnected-(U5-GN2-Pad8)") (class "Default")
      (node (ref "U5") (pin "8") (pinfunction "GN2_8") (pintype "bidirectional"))
    )
  )
)
